# Sheet1.net
KiCad netlist of a schematic drawn in Altium Designer
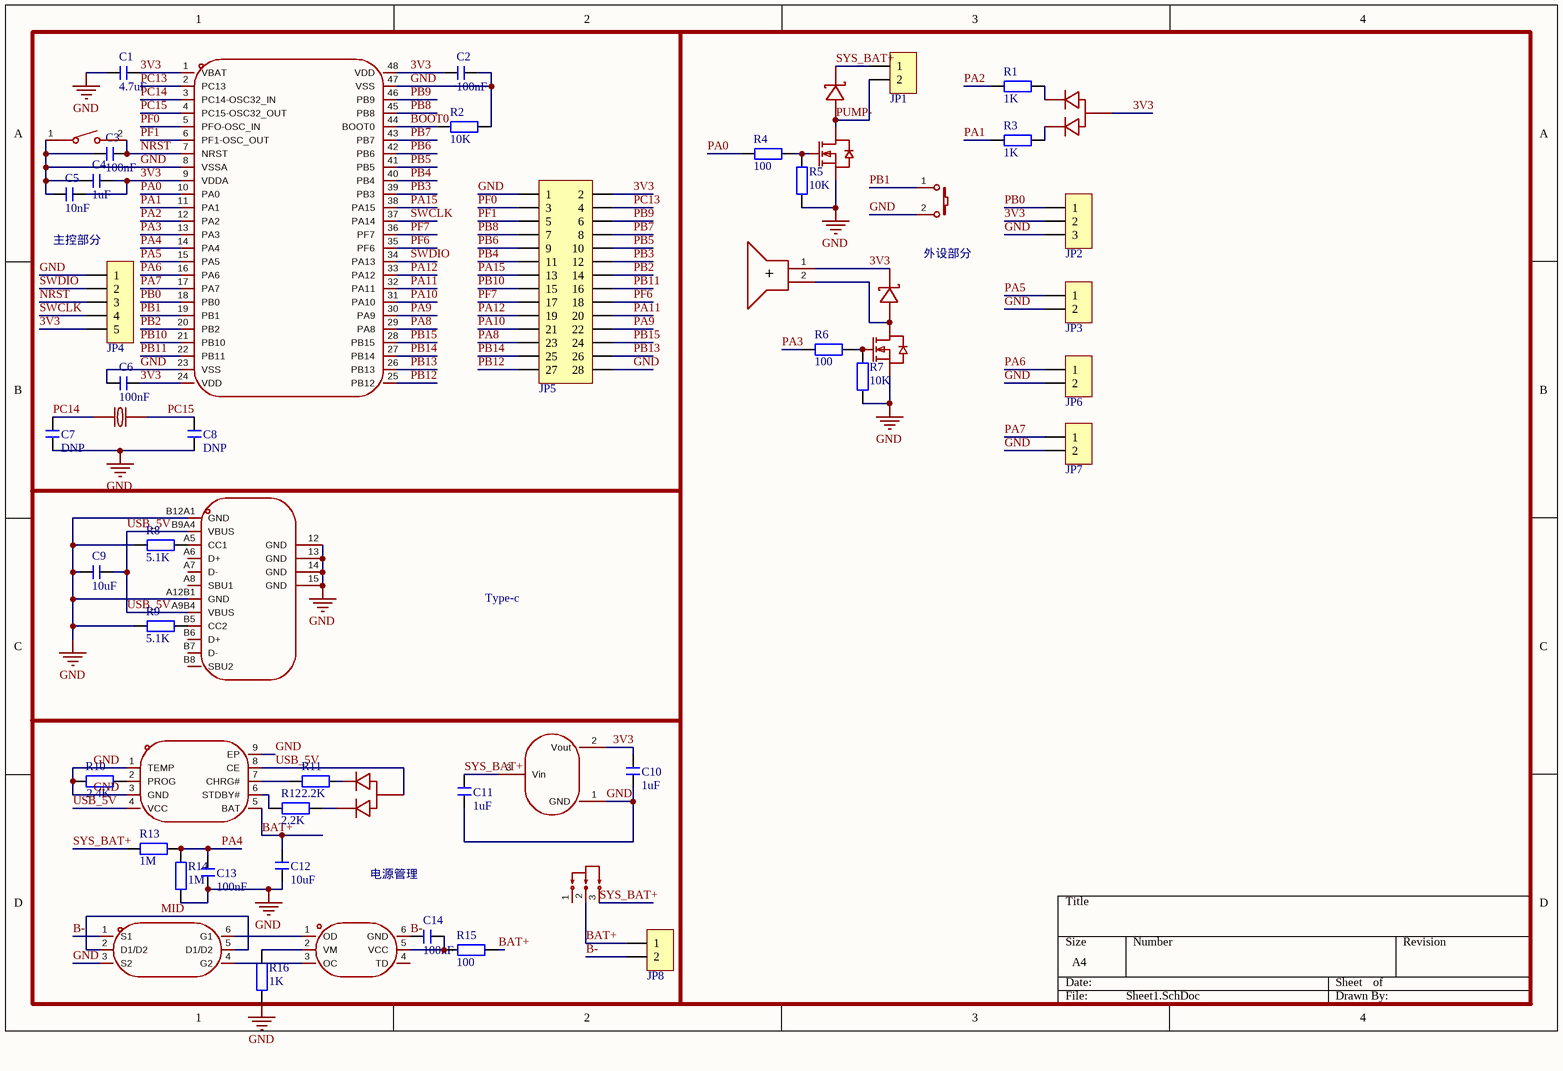
[diagram p0: Sheet1.SchDoc]

(export (version "E")
  (design (tool "Eeschema 10.0.6"))
  (components
    (comp (ref "BUZZER1")
      (value "hnb09a03")
      (footprint "BUZ-TH_BD9.0-P5.00-D0.6-FD")
      (description "驱动方式:有源(内含驱动线路);构造类型:电磁式;额定电压:3V;频率:3kHz;声压(SPL):85dB;")
      (fields (field (name "MANUFACTURER") "华能") (field (name "MANUFACTURERPART") "HNB09A03"))
      (libsource (lib "altium-import") (part "root_2_mirrored_hnb09a03_"))
    )
    (comp (ref "C1")
      (value "4.7uF")
      (footprint "C 0603_L")
      (description "贴片电容")
      (libsource (lib "0.1 - 电阻-电容-电感") (part "C"))
    )
    (comp (ref "C2")
      (value "100nF")
      (footprint "C 0603_L")
      (description "贴片电容")
      (libsource (lib "0.1 - 电阻-电容-电感") (part "C"))
    )
    (comp (ref "C3")
      (value "100nF")
      (footprint "C 0603_L")
      (description "贴片电容")
      (libsource (lib "0.1 - 电阻-电容-电感") (part "C"))
    )
    (comp (ref "C4")
      (value "1uF")
      (footprint "C 0603_L")
      (description "贴片电容")
      (libsource (lib "0.1 - 电阻-电容-电感") (part "C"))
    )
    (comp (ref "C5")
      (value "10nF")
      (footprint "C 0603_L")
      (description "贴片电容")
      (libsource (lib "0.1 - 电阻-电容-电感") (part "C"))
    )
    (comp (ref "C6")
      (value "100nF")
      (footprint "C 0603_L")
      (description "贴片电容")
      (libsource (lib "0.1 - 电阻-电容-电感") (part "C"))
    )
    (comp (ref "C7")
      (value "DNP")
      (footprint "C 0603_L")
      (description "贴片电容")
      (libsource (lib "0.1 - 电阻-电容-电感") (part "C"))
    )
    (comp (ref "C8")
      (value "DNP")
      (footprint "C 0603_L")
      (description "贴片电容")
      (libsource (lib "0.1 - 电阻-电容-电感") (part "C"))
    )
    (comp (ref "C9")
      (value "10uF")
      (footprint "C 0603_L")
      (description "贴片电容")
      (libsource (lib "Schlib1") (part "C"))
    )
    (comp (ref "C10")
      (value "1uF")
      (footprint "C 0603_L")
      (description "贴片电容")
      (libsource (lib "Schlib1") (part "C"))
    )
    (comp (ref "C11")
      (value "1uF")
      (footprint "C 0603_L")
      (description "贴片电容")
      (libsource (lib "Schlib1") (part "C"))
    )
    (comp (ref "C12")
      (value "10uF")
      (footprint "C 0603_L")
      (description "贴片电容")
      (libsource (lib "0.1 - 电阻-电容-电感") (part "C"))
    )
    (comp (ref "C13")
      (value "100nF")
      (footprint "C 0603_L")
      (description "贴片电容")
      (libsource (lib "0.1 - 电阻-电容-电感") (part "C"))
    )
    (comp (ref "C14")
      (value "100nF")
      (footprint "C 0603_L")
      (description "贴片电容")
      (libsource (lib "0.1 - 电阻-电容-电感") (part "C"))
    )
    (comp (ref "Charge_LED")
      (value "tj-l5fytxhtcylc2r2g-a5")
      (footprint "LED-TH_3P-BD5.9-P2.54-BI")
      (fields
        (field (name "MANUFACTURER") "TOGIALED(统佳)")
        (field (name "MANUFACTURERPART") "TJ-L5FYTXHTCYLC2R2G-A5")
      )
      (libsource (lib "altium-import") (part "root_3_tj-l5fytxhtcylc2r2g-a5_"))
    )
    (comp (ref "D1")
      (value "ss14_c83852")
      (footprint "SMA_L4.3-W2.6-LS5.2-RD")
      (description "正向压降(Vf):500mV@1A;直流反向耐压(Vr):40V;整流电流:1A;")
      (fields (field (name "MANUFACTURER") "onsemi(安森美)") (field (name "MANUFACTURERPART") "SS14"))
      (libsource (lib "Schlib1") (part "ss14_c83852"))
    )
    (comp (ref "D2")
      (value "ss14_c83852")
      (footprint "SMA_L4.3-W2.6-LS5.2-RD")
      (description "正向压降(Vf):500mV@1A;直流反向耐压(Vr):40V;整流电流:1A;")
      (fields (field (name "MANUFACTURER") "onsemi(安森美)") (field (name "MANUFACTURERPART") "SS14"))
      (libsource (lib "Schlib1") (part "ss14_c83852"))
    )
    (comp (ref "Function_LED")
      (value "tj-l5fytxhtcylc2r2g-a5")
      (footprint "LED-TH_3P-BD5.9-P2.54-BI")
      (fields
        (field (name "MANUFACTURER") "TOGIALED(统佳)")
        (field (name "MANUFACTURERPART") "TJ-L5FYTXHTCYLC2R2G-A5")
      )
      (libsource (lib "altium-import") (part "root_3_tj-l5fytxhtcylc2r2g-a5_"))
    )
    (comp (ref "JP1")
      (value "HDR-1X2")
      (footprint "XH2.54-LI-2P")
      (description "2P接插件")
      (fields (field (name "版权归属") "封装库来自淘宝 ID：黄晶宝石"))
      (libsource (lib "5.3 - 接插件-脚距2.54 (100mil) ") (part "Header 2"))
    )
    (comp (ref "JP2")
      (value "HDR-1X3")
      (footprint "HDR2.54-LI-3P")
      (description "3P接插件")
      (fields (field (name "版权归属") "封装库来自淘宝 ID：黄晶宝石"))
      (libsource (lib "5.3 - 接插件-脚距2.54 (100mil) ") (part "Header 3"))
    )
    (comp (ref "JP3")
      (value "HDR-1X2")
      (footprint "XH2.54-LI-2P")
      (description "2P接插件")
      (fields (field (name "版权归属") "封装库来自淘宝 ID：黄晶宝石"))
      (libsource (lib "5.3 - 接插件-脚距2.54 (100mil) ") (part "Header 2"))
    )
    (comp (ref "JP4")
      (value "HDR-1X5")
      (footprint "HDR2.54-LI-5P")
      (description "5P接插件")
      (fields (field (name "版权归属") "封装库来自淘宝 ID：黄晶宝石"))
      (libsource (lib "5.3 - 接插件-脚距2.54 (100mil) ") (part "Header 5"))
    )
    (comp (ref "JP5")
      (value "Header 2X11")
      (footprint "HDR2.54-LI-2x14P")
      (description "14*2P接插件")
      (fields (field (name "版权归属") "源创客"))
      (libsource (lib "5.3 - 接插件-脚距2.54 (100mil) ") (part "Header 14X2"))
    )
    (comp (ref "JP6")
      (value "HDR-1X2")
      (footprint "XH2.54-LI-2P")
      (description "2P接插件")
      (fields (field (name "版权归属") "封装库来自淘宝 ID：黄晶宝石"))
      (libsource (lib "5.3 - 接插件-脚距2.54 (100mil) ") (part "Header 2"))
    )
    (comp (ref "JP7")
      (value "HDR-1X2")
      (footprint "XH2.54-LI-2P")
      (description "2P接插件")
      (fields (field (name "版权归属") "封装库来自淘宝 ID：黄晶宝石"))
      (libsource (lib "5.3 - 接插件-脚距2.54 (100mil) ") (part "Header 2"))
    )
    (comp (ref "JP8")
      (value "HDR-1X2")
      (footprint "XH2.54-LI-2P")
      (description "2P接插件")
      (fields (field (name "版权归属") "封装库来自淘宝 ID：黄晶宝石"))
      (libsource (lib "5.3 - 接插件-脚距2.54 (100mil) ") (part "Header 2"))
    )
    (comp (ref "Q1")
      (value "ao3400a_c347475")
      (footprint "SOT-23-3_L2.9-W1.3-P1.90-LS2.4-BR")
      (description "数量:1个N沟道;漏源电压(Vdss):30V;连续漏极电流(Id):5.8A;导通电阻(RDS(on)):17mΩ@10V;耗散功率(Pd):1.4W;阈值电压(Vgs(th)):1.1V;")
      (fields (field (name "MANUFACTURER") "UMW(友台半导体)") (field (name "MANUFACTURERPART") "AO3400A"))
      (libsource (lib "Schlib1") (part "ao3400a_c347475"))
    )
    (comp (ref "Q2")
      (value "ao3400a_c347475")
      (footprint "SOT-23-3_L2.9-W1.3-P1.90-LS2.4-BR")
      (description "数量:1个N沟道;漏源电压(Vdss):30V;连续漏极电流(Id):5.8A;导通电阻(RDS(on)):17mΩ@10V;耗散功率(Pd):1.4W;阈值电压(Vgs(th)):1.1V;")
      (fields (field (name "MANUFACTURER") "UMW(友台半导体)") (field (name "MANUFACTURERPART") "AO3400A"))
      (libsource (lib "Schlib1") (part "ao3400a_c347475"))
    )
    (comp (ref "Q3")
      (value "fs8205a")
      (footprint "SOT-23-6_L2.9-W1.6-P0.95-LS2.8-BR")
      (fields (field (name "MANUFACTURER") "TECH PUBLIC(台舟)") (field (name "MANUFACTURERPART") "FS8205A"))
      (libsource (lib "Schlib1") (part "fs8205a"))
    )
    (comp (ref "R1")
      (value "1K")
      (footprint "R 0603_L")
      (description "贴片电阻")
      (fields (field (name "版权归属") "来自淘宝 ID：黄晶宝石"))
      (libsource (lib "0.1 - 电阻-电容-电感") (part "R"))
    )
    (comp (ref "R2")
      (value "10K")
      (footprint "R 0603_L")
      (description "贴片电阻")
      (fields (field (name "版权归属") "来自淘宝 ID：黄晶宝石"))
      (libsource (lib "0.1 - 电阻-电容-电感") (part "R"))
    )
    (comp (ref "R3")
      (value "1K")
      (footprint "R 0603_L")
      (description "贴片电阻")
      (fields (field (name "版权归属") "来自淘宝 ID：黄晶宝石"))
      (libsource (lib "0.1 - 电阻-电容-电感") (part "R"))
    )
    (comp (ref "R4")
      (value "100")
      (footprint "R 0603_L")
      (description "贴片电阻")
      (fields (field (name "版权归属") "来自淘宝 ID：黄晶宝石"))
      (libsource (lib "0.1 - 电阻-电容-电感") (part "R"))
    )
    (comp (ref "R5")
      (value "10K")
      (footprint "R 0603_L")
      (description "贴片电阻")
      (fields (field (name "版权归属") "来自淘宝 ID：黄晶宝石"))
      (libsource (lib "0.1 - 电阻-电容-电感") (part "R"))
    )
    (comp (ref "R6")
      (value "100")
      (footprint "R 0603_L")
      (description "贴片电阻")
      (fields (field (name "版权归属") "来自淘宝 ID：黄晶宝石"))
      (libsource (lib "0.1 - 电阻-电容-电感") (part "R"))
    )
    (comp (ref "R7")
      (value "10K")
      (footprint "R 0603_L")
      (description "贴片电阻")
      (fields (field (name "版权归属") "来自淘宝 ID：黄晶宝石"))
      (libsource (lib "0.1 - 电阻-电容-电感") (part "R"))
    )
    (comp (ref "R8")
      (value "5.1K")
      (footprint "R 0603_L")
      (description "贴片电阻")
      (fields (field (name "版权归属") "来自淘宝 ID：黄晶宝石"))
      (libsource (lib "0.1 - 电阻-电容-电感") (part "R"))
    )
    (comp (ref "R9")
      (value "5.1K")
      (footprint "R 0603_L")
      (description "贴片电阻")
      (fields (field (name "版权归属") "来自淘宝 ID：黄晶宝石"))
      (libsource (lib "0.1 - 电阻-电容-电感") (part "R"))
    )
    (comp (ref "R10")
      (value "2.4K")
      (footprint "R 0603_L")
      (description "贴片电阻")
      (fields (field (name "版权归属") "来自淘宝 ID：黄晶宝石"))
      (libsource (lib "0.1 - 电阻-电容-电感") (part "R"))
    )
    (comp (ref "R11")
      (value "2.2K")
      (footprint "R 0603_L")
      (description "贴片电阻")
      (fields (field (name "版权归属") "来自淘宝 ID：黄晶宝石"))
      (libsource (lib "0.1 - 电阻-电容-电感") (part "R"))
    )
    (comp (ref "R12")
      (value "2.2K")
      (footprint "R 0603_L")
      (description "贴片电阻")
      (fields (field (name "版权归属") "来自淘宝 ID：黄晶宝石"))
      (libsource (lib "0.1 - 电阻-电容-电感") (part "R"))
    )
    (comp (ref "R13")
      (value "1M")
      (footprint "R 0603_L")
      (description "贴片电阻")
      (fields (field (name "版权归属") "来自淘宝 ID：黄晶宝石"))
      (libsource (lib "0.1 - 电阻-电容-电感") (part "R"))
    )
    (comp (ref "R14")
      (value "1M")
      (footprint "R 0603_L")
      (description "贴片电阻")
      (fields (field (name "版权归属") "来自淘宝 ID：黄晶宝石"))
      (libsource (lib "0.1 - 电阻-电容-电感") (part "R"))
    )
    (comp (ref "R15")
      (value "100")
      (footprint "R 0603_L")
      (description "贴片电阻")
      (fields (field (name "版权归属") "来自淘宝 ID：黄晶宝石"))
      (libsource (lib "0.1 - 电阻-电容-电感") (part "R"))
    )
    (comp (ref "R16")
      (value "1K")
      (footprint "R 0603_L")
      (description "贴片电阻")
      (fields (field (name "版权归属") "来自淘宝 ID：黄晶宝石"))
      (libsource (lib "0.1 - 电阻-电容-电感") (part "R"))
    )
    (comp (ref "SW1")
      (value "ts-1088-ar02016")
      (footprint "SW-SMD_L3.9-W3.0-P4.45")
      (fields (field (name "MANUFACTURER") "XUNPU(讯普)") (field (name "MANUFACTURERPART") "TS-1088-AR02016"))
      (libsource (lib "Schlib1") (part "ts-1088-ar02016"))
    )
    (comp (ref "SW2")
      (value "mx1a-11nw")
      (footprint "SW-TH_MX1A-11NW")
      (fields (field (name "MANUFACTURER") "CHERRY") (field (name "MANUFACTURERPART") "MX1A-11NW"))
      (libsource (lib "altium-import") (part "root_3_mx1a-11nw_"))
    )
    (comp (ref "U1")
      (value "stm32f031c6t6")
      (footprint "LQFP-48_L7.0-W7.0-P0.50-LS9.0-BL")
      (description "CPU内核:ARM Cortex-M0;CPU最大主频:48MHz;CPU位数:32 Bit;")
      (fields (field (name "MANUFACTURER") "ST(意法半导体)") (field (name "MANUFACTURERPART") "STM32F031C6T6"))
      (libsource (lib "Schlib1") (part "stm32f031c6t6"))
    )
    (comp (ref "U2")
      (value "xc6206p332mr-g_c5446")
      (footprint "SOT-23-3_L2.9-W1.6-P1.90-LS2.8-BR")
      (description "输出极性:正极;工作电压:6V;输出电压:3.3V;输出电流:200mA;电源纹波抑制比(PSRR):-;输出类型:固定;")
      (fields (field (name "MANUFACTURER") "TOREX(特瑞仕)") (field (name "MANUFACTURERPART") "XC6206P332MR-G"))
      (libsource (lib "Schlib1") (part "xc6206p332mr-g_c5446"))
    )
    (comp (ref "U3")
      (value "tp4056_c382139")
      (footprint "ESOP-8_L4.9-W3.9-P1.27-LS6.0-BL-EP")
      (description "工作电压:4V~6V;最大充电电流:1A;电池类型:锂电池;电池节数:1;")
      (fields (field (name "MANUFACTURER") "TPOWER(天源)") (field (name "MANUFACTURERPART") "TP4056"))
      (libsource (lib "Schlib1") (part "tp4056_c382139"))
    )
    (comp (ref "U4")
      (value "hx ss12d10g5")
      (footprint "SW-TH_3P-P4.80-HX-SS12D10G4")
      (description "电路结构:单刀双掷;安装方式:直插;开关颜色:黑色;额定电流:2A;额定电压:125V;工作寿命:1万次;")
      (fields (field (name "MANUFACTURER") "hanxia(韩下)") (field (name "MANUFACTURERPART") "HX SS12D10G5"))
      (libsource (lib "altium-import") (part "root_0_hx ss12d10g5_"))
    )
    (comp (ref "U5")
      (value "dw01a_c351410")
      (footprint "SOT-23-6_L2.9-W1.6-P0.95-LS2.8-BL")
      (description "工作电压:300mV~10V;最大充电电流:-;电池类型:锂电池;电池节数:1;")
      (fields (field (name "MANUFACTURER") "PUOLOP(迪浦)") (field (name "MANUFACTURERPART") "DW01A"))
      (libsource (lib "Schlib1") (part "dw01a_c351410"))
    )
    (comp (ref "USB1")
      (value "typec-16p_c53207138")
      (footprint "USB-C-SMD_TYPEC-16P_C53207138")
      (description "连接器类型:Type-C;协议标准:-;公母:母;安装方式:卧贴;触点数量:16P;端口数量:1;额定电流 - 电源:3A;工作温度:-40℃~+85℃;")
      (fields (field (name "MANUFACTURER") "BXCONN(宝讯)") (field (name "MANUFACTURERPART") "TYPEC-16P"))
      (libsource (lib "Schlib1") (part "typec-16p_c53207138"))
    )
    (comp (ref "X1")
      (value "q13fc13500004_c32346")
      (footprint "FC-135R_L3.2-W1.5")
      (description "晶振类型:贴片晶振;频率:32.768kHz;常温频差:±20ppm;负载电容:12.5pF;")
      (fields (field (name "MANUFACTURER") "EPSON(爱普生)") (field (name "MANUFACTURERPART") "Q13FC13500004"))
      (libsource (lib "altium-import") (part "root_0_q13fc13500004_c32346_"))
    )
  )
  (nets
    (net (code "1") (name "/3V3") (class "Default")
      (node (ref "BUZZER1") (pin "1") (pinfunction "+_1") (pintype "passive"))
      (node (ref "C1") (pin "2") (pinfunction "2_2") (pintype "passive"))
      (node (ref "C10") (pin "2") (pinfunction "2_2") (pintype "passive"))
      (node (ref "C2") (pin "1") (pinfunction "1_1") (pintype "passive"))
      (node (ref "C4") (pin "2") (pinfunction "2_2") (pintype "passive"))
      (node (ref "C5") (pin "2") (pinfunction "2_2") (pintype "passive"))
      (node (ref "C6") (pin "2") (pinfunction "2_2") (pintype "passive"))
      (node (ref "D2") (pin "1") (pinfunction "K_1") (pintype "passive"))
      (node (ref "Function_LED") (pin "2") (pinfunction "+_2") (pintype "passive"))
      (node (ref "JP2") (pin "2") (pinfunction "2_2") (pintype "passive"))
      (node (ref "JP4") (pin "5") (pinfunction "5_5") (pintype "passive"))
      (node (ref "JP5") (pin "2") (pinfunction "2_2") (pintype "passive"))
      (node (ref "U1") (pin "1") (pinfunction "VBAT_1") (pintype "passive"))
      (node (ref "U1") (pin "24") (pinfunction "VDD_24") (pintype "passive"))
      (node (ref "U1") (pin "48") (pinfunction "VDD_48") (pintype "passive"))
      (node (ref "U1") (pin "9") (pinfunction "VDDA_9") (pintype "passive"))
      (node (ref "U2") (pin "2") (pinfunction "Vout_2") (pintype "passive"))
    )
    (net (code "2") (name "/B-") (class "Default")
      (node (ref "C14") (pin "2") (pinfunction "2_2") (pintype "passive"))
      (node (ref "JP8") (pin "2") (pinfunction "2_2") (pintype "passive"))
      (node (ref "Q3") (pin "1") (pinfunction "S1_1") (pintype "passive"))
      (node (ref "U5") (pin "6") (pinfunction "GND_6") (pintype "passive"))
    )
    (net (code "3") (name "/BAT+") (class "Default")
      (node (ref "C12") (pin "2") (pinfunction "2_2") (pintype "passive"))
      (node (ref "JP8") (pin "1") (pinfunction "1_1") (pintype "passive"))
      (node (ref "R15") (pin "1") (pinfunction "1_1") (pintype "passive"))
      (node (ref "U3") (pin "5") (pinfunction "BAT_5") (pintype "passive"))
      (node (ref "U4") (pin "2") (pinfunction "2_2") (pintype "passive"))
    )
    (net (code "4") (name "/BOOT0") (class "Default")
      (node (ref "R2") (pin "1") (pinfunction "1_1") (pintype "passive"))
      (node (ref "U1") (pin "44") (pinfunction "BOOT0_44") (pintype "passive"))
    )
    (net (code "5") (name "/MID") (class "Default")
      (node (ref "Q3") (pin "2") (pinfunction "D1/D2_2") (pintype "passive"))
      (node (ref "Q3") (pin "5") (pinfunction "D1/D2_5") (pintype "passive"))
    )
    (net (code "6") (name "/NRST") (class "Default")
      (node (ref "C3") (pin "2") (pinfunction "2_2") (pintype "passive"))
      (node (ref "JP4") (pin "3") (pinfunction "3_3") (pintype "passive"))
      (node (ref "SW1") (pin "2") (pinfunction "2_2") (pintype "passive"))
      (node (ref "U1") (pin "7") (pinfunction "NRST_7") (pintype "passive"))
    )
    (net (code "7") (name "/PA0") (class "Default")
      (node (ref "R4") (pin "1") (pinfunction "1_1") (pintype "passive"))
      (node (ref "U1") (pin "10") (pinfunction "PA0_10") (pintype "passive"))
    )
    (net (code "8") (name "/PA1") (class "Default")
      (node (ref "R3") (pin "2") (pinfunction "2_2") (pintype "passive"))
      (node (ref "U1") (pin "11") (pinfunction "PA1_11") (pintype "passive"))
    )
    (net (code "9") (name "/PA2") (class "Default")
      (node (ref "R1") (pin "2") (pinfunction "2_2") (pintype "passive"))
      (node (ref "U1") (pin "12") (pinfunction "PA2_12") (pintype "passive"))
    )
    (net (code "10") (name "/PA3") (class "Default")
      (node (ref "R6") (pin "2") (pinfunction "2_2") (pintype "passive"))
      (node (ref "U1") (pin "13") (pinfunction "PA3_13") (pintype "passive"))
    )
    (net (code "11") (name "/PA4") (class "Default")
      (node (ref "C13") (pin "2") (pinfunction "2_2") (pintype "passive"))
      (node (ref "R13") (pin "1") (pinfunction "1_1") (pintype "passive"))
      (node (ref "R14") (pin "2") (pinfunction "2_2") (pintype "passive"))
      (node (ref "U1") (pin "14") (pinfunction "PA4_14") (pintype "passive"))
    )
    (net (code "12") (name "/PA5") (class "Default")
      (node (ref "JP3") (pin "1") (pinfunction "1_1") (pintype "passive"))
      (node (ref "U1") (pin "15") (pinfunction "PA5_15") (pintype "passive"))
    )
    (net (code "13") (name "/PA6") (class "Default")
      (node (ref "JP6") (pin "1") (pinfunction "1_1") (pintype "passive"))
      (node (ref "U1") (pin "16") (pinfunction "PA6_16") (pintype "passive"))
    )
    (net (code "14") (name "/PA7") (class "Default")
      (node (ref "JP7") (pin "1") (pinfunction "1_1") (pintype "passive"))
      (node (ref "U1") (pin "17") (pinfunction "PA7_17") (pintype "passive"))
    )
    (net (code "15") (name "/PA8") (class "Default")
      (node (ref "JP5") (pin "23") (pinfunction "23_23") (pintype "passive"))
      (node (ref "U1") (pin "29") (pinfunction "PA8_29") (pintype "passive"))
    )
    (net (code "16") (name "/PA9") (class "Default")
      (node (ref "JP5") (pin "22") (pinfunction "22_22") (pintype "passive"))
      (node (ref "U1") (pin "30") (pinfunction "PA9_30") (pintype "passive"))
    )
    (net (code "17") (name "/PA10") (class "Default")
      (node (ref "JP5") (pin "21") (pinfunction "21_21") (pintype "passive"))
      (node (ref "U1") (pin "31") (pinfunction "PA10_31") (pintype "passive"))
    )
    (net (code "18") (name "/PA11") (class "Default")
      (node (ref "JP5") (pin "20") (pinfunction "20_20") (pintype "passive"))
      (node (ref "U1") (pin "32") (pinfunction "PA11_32") (pintype "passive"))
    )
    (net (code "19") (name "/PA12") (class "Default")
      (node (ref "JP5") (pin "19") (pinfunction "19_19") (pintype "passive"))
      (node (ref "U1") (pin "33") (pinfunction "PA12_33") (pintype "passive"))
    )
    (net (code "20") (name "/PA15") (class "Default")
      (node (ref "JP5") (pin "13") (pinfunction "13_13") (pintype "passive"))
      (node (ref "U1") (pin "38") (pinfunction "PA15_38") (pintype "passive"))
    )
    (net (code "21") (name "/PB0") (class "Default")
      (node (ref "JP2") (pin "1") (pinfunction "1_1") (pintype "passive"))
      (node (ref "U1") (pin "18") (pinfunction "PB0_18") (pintype "passive"))
    )
    (net (code "22") (name "/PB1") (class "Default")
      (node (ref "SW2") (pin "1") (pinfunction "1_1") (pintype "passive"))
      (node (ref "U1") (pin "19") (pinfunction "PB1_19") (pintype "passive"))
    )
    (net (code "23") (name "/PB2") (class "Default")
      (node (ref "JP5") (pin "14") (pinfunction "14_14") (pintype "passive"))
      (node (ref "U1") (pin "20") (pinfunction "PB2_20") (pintype "passive"))
    )
    (net (code "24") (name "/PB3") (class "Default")
      (node (ref "JP5") (pin "12") (pinfunction "12_12") (pintype "passive"))
      (node (ref "U1") (pin "39") (pinfunction "PB3_39") (pintype "passive"))
    )
    (net (code "25") (name "/PB4") (class "Default")
      (node (ref "JP5") (pin "11") (pinfunction "11_11") (pintype "passive"))
      (node (ref "U1") (pin "40") (pinfunction "PB4_40") (pintype "passive"))
    )
    (net (code "26") (name "/PB5") (class "Default")
      (node (ref "JP5") (pin "10") (pinfunction "10_10") (pintype "passive"))
      (node (ref "U1") (pin "41") (pinfunction "PB5_41") (pintype "passive"))
    )
    (net (code "27") (name "/PB6") (class "Default")
      (node (ref "JP5") (pin "9") (pinfunction "9_9") (pintype "passive"))
      (node (ref "U1") (pin "42") (pinfunction "PB6_42") (pintype "passive"))
    )
    (net (code "28") (name "/PB7") (class "Default")
      (node (ref "JP5") (pin "8") (pinfunction "8_8") (pintype "passive"))
      (node (ref "U1") (pin "43") (pinfunction "PB7_43") (pintype "passive"))
    )
    (net (code "29") (name "/PB8") (class "Default")
      (node (ref "JP5") (pin "7") (pinfunction "7_7") (pintype "passive"))
      (node (ref "U1") (pin "45") (pinfunction "PB8_45") (pintype "passive"))
    )
    (net (code "30") (name "/PB9") (class "Default")
      (node (ref "JP5") (pin "6") (pinfunction "6_6") (pintype "passive"))
      (node (ref "U1") (pin "46") (pinfunction "PB9_46") (pintype "passive"))
    )
    (net (code "31") (name "/PB10") (class "Default")
      (node (ref "JP5") (pin "15") (pinfunction "15_15") (pintype "passive"))
      (node (ref "U1") (pin "21") (pinfunction "PB10_21") (pintype "passive"))
    )
    (net (code "32") (name "/PB11") (class "Default")
      (node (ref "JP5") (pin "16") (pinfunction "16_16") (pintype "passive"))
      (node (ref "U1") (pin "22") (pinfunction "PB11_22") (pintype "passive"))
    )
    (net (code "33") (name "/PB12") (class "Default")
      (node (ref "JP5") (pin "27") (pinfunction "27_27") (pintype "passive"))
      (node (ref "U1") (pin "25") (pinfunction "PB12_25") (pintype "passive"))
    )
    (net (code "34") (name "/PB13") (class "Default")
      (node (ref "JP5") (pin "26") (pinfunction "26_26") (pintype "passive"))
      (node (ref "U1") (pin "26") (pinfunction "PB13_26") (pintype "passive"))
    )
    (net (code "35") (name "/PB14") (class "Default")
      (node (ref "JP5") (pin "25") (pinfunction "25_25") (pintype "passive"))
      (node (ref "U1") (pin "27") (pinfunction "PB14_27") (pintype "passive"))
    )
    (net (code "36") (name "/PB15") (class "Default")
      (node (ref "JP5") (pin "24") (pinfunction "24_24") (pintype "passive"))
      (node (ref "U1") (pin "28") (pinfunction "PB15_28") (pintype "passive"))
    )
    (net (code "37") (name "/PC13") (class "Default")
      (node (ref "JP5") (pin "4") (pinfunction "4_4") (pintype "passive"))
      (node (ref "U1") (pin "2") (pinfunction "PC13_2") (pintype "passive"))
    )
    (net (code "38") (name "/PC14") (class "Default")
      (node (ref "C7") (pin "2") (pinfunction "2_2") (pintype "passive"))
      (node (ref "U1") (pin "3") (pinfunction "PC14-OSC32_IN_3") (pintype "passive"))
      (node (ref "X1") (pin "1") (pinfunction "1_1") (pintype "passive"))
    )
    (net (code "39") (name "/PC15") (class "Default")
      (node (ref "C8") (pin "2") (pinfunction "2_2") (pintype "passive"))
      (node (ref "U1") (pin "4") (pinfunction "PC15-OSC32_OUT_4") (pintype "passive"))
      (node (ref "X1") (pin "2") (pinfunction "2_2") (pintype "passive"))
    )
    (net (code "40") (name "/PF0") (class "Default")
      (node (ref "JP5") (pin "3") (pinfunction "3_3") (pintype "passive"))
      (node (ref "U1") (pin "5") (pinfunction "PFO-OSC_IN_5") (pintype "passive"))
    )
    (net (code "41") (name "/PF1") (class "Default")
      (node (ref "JP5") (pin "5") (pinfunction "5_5") (pintype "passive"))
      (node (ref "U1") (pin "6") (pinfunction "PF1-OSC_OUT_6") (pintype "passive"))
    )
    (net (code "42") (name "/PF6") (class "Default")
      (node (ref "JP5") (pin "18") (pinfunction "18_18") (pintype "passive"))
      (node (ref "U1") (pin "35") (pinfunction "PF6_35") (pintype "passive"))
    )
    (net (code "43") (name "/PF7") (class "Default")
      (node (ref "JP5") (pin "17") (pinfunction "17_17") (pintype "passive"))
      (node (ref "U1") (pin "36") (pinfunction "PF7_36") (pintype "passive"))
    )
    (net (code "44") (name "/PUMP-") (class "Default")
      (node (ref "D1") (pin "2") (pinfunction "A_2") (pintype "passive"))
      (node (ref "JP1") (pin "2") (pinfunction "2_2") (pintype "passive"))
      (node (ref "Q1") (pin "3") (pinfunction "D_3") (pintype "passive"))
    )
    (net (code "45") (name "/SWCLK") (class "Default")
      (node (ref "JP4") (pin "4") (pinfunction "4_4") (pintype "passive"))
      (node (ref "U1") (pin "37") (pinfunction "PA14_37") (pintype "passive"))
    )
    (net (code "46") (name "/SWDIO") (class "Default")
      (node (ref "JP4") (pin "2") (pinfunction "2_2") (pintype "passive"))
      (node (ref "U1") (pin "34") (pinfunction "PA13_34") (pintype "passive"))
    )
    (net (code "47") (name "/SYS_BAT+") (class "Default")
      (node (ref "C11") (pin "2") (pinfunction "2_2") (pintype "passive"))
      (node (ref "D1") (pin "1") (pinfunction "K_1") (pintype "passive"))
      (node (ref "JP1") (pin "1") (pinfunction "1_1") (pintype "passive"))
      (node (ref "R13") (pin "2") (pinfunction "2_2") (pintype "passive"))
      (node (ref "U2") (pin "3") (pinfunction "Vin_3") (pintype "passive"))
      (node (ref "U4") (pin "3") (pinfunction "3_3") (pintype "passive"))
    )
    (net (code "48") (name "/USB_5V") (class "Default")
      (node (ref "C9") (pin "2") (pinfunction "2_2") (pintype "passive"))
      (node (ref "Charge_LED") (pin "2") (pinfunction "+_2") (pintype "passive"))
      (node (ref "U3") (pin "4") (pinfunction "VCC_4") (pintype "passive"))
      (node (ref "U3") (pin "8") (pinfunction "CE_8") (pintype "passive"))
      (node (ref "USB1") (pin "A9B4") (pinfunction "VBUS_A9B4") (pintype "passive"))
      (node (ref "USB1") (pin "B9A4") (pinfunction "VBUS_B9A4") (pintype "passive"))
    )
    (net (code "49") (name "GND") (class "Default")
      (node (ref "C1") (pin "1") (pinfunction "1_1") (pintype "passive"))
      (node (ref "C10") (pin "1") (pinfunction "1_1") (pintype "passive"))
      (node (ref "C11") (pin "1") (pinfunction "1_1") (pintype "passive"))
      (node (ref "C12") (pin "1") (pinfunction "1_1") (pintype "passive"))
      (node (ref "C13") (pin "1") (pinfunction "1_1") (pintype "passive"))
      (node (ref "C2") (pin "2") (pinfunction "2_2") (pintype "passive"))
      (node (ref "C3") (pin "1") (pinfunction "1_1") (pintype "passive"))
      (node (ref "C4") (pin "1") (pinfunction "1_1") (pintype "passive"))
      (node (ref "C5") (pin "1") (pinfunction "1_1") (pintype "passive"))
      (node (ref "C6") (pin "1") (pinfunction "1_1") (pintype "passive"))
      (node (ref "C7") (pin "1") (pinfunction "1_1") (pintype "passive"))
      (node (ref "C8") (pin "1") (pinfunction "1_1") (pintype "passive"))
      (node (ref "C9") (pin "1") (pinfunction "1_1") (pintype "passive"))
      (node (ref "JP2") (pin "3") (pinfunction "3_3") (pintype "passive"))
      (node (ref "JP3") (pin "2") (pinfunction "2_2") (pintype "passive"))
      (node (ref "JP4") (pin "1") (pinfunction "1_1") (pintype "passive"))
      (node (ref "JP5") (pin "1") (pinfunction "1_1") (pintype "passive"))
      (node (ref "JP5") (pin "28") (pinfunction "28_28") (pintype "passive"))
      (node (ref "JP6") (pin "2") (pinfunction "2_2") (pintype "passive"))
      (node (ref "JP7") (pin "2") (pinfunction "2_2") (pintype "passive"))
      (node (ref "Q1") (pin "2") (pinfunction "S_2") (pintype "passive"))
      (node (ref "Q2") (pin "2") (pinfunction "S_2") (pintype "passive"))
      (node (ref "Q3") (pin "3") (pinfunction "S2_3") (pintype "passive"))
      (node (ref "R10") (pin "1") (pinfunction "1_1") (pintype "passive"))
      (node (ref "R14") (pin "1") (pinfunction "1_1") (pintype "passive"))
      (node (ref "R16") (pin "1") (pinfunction "1_1") (pintype "passive"))
      (node (ref "R2") (pin "2") (pinfunction "2_2") (pintype "passive"))
      (node (ref "R5") (pin "1") (pinfunction "1_1") (pintype "passive"))
      (node (ref "R7") (pin "1") (pinfunction "1_1") (pintype "passive"))
      (node (ref "R8") (pin "1") (pinfunction "1_1") (pintype "passive"))
      (node (ref "R9") (pin "1") (pinfunction "1_1") (pintype "passive"))
      (node (ref "SW1") (pin "1") (pinfunction "1_1") (pintype "passive"))
      (node (ref "SW2") (pin "2") (pinfunction "2_2") (pintype "passive"))
      (node (ref "U1") (pin "23") (pinfunction "VSS_23") (pintype "passive"))
      (node (ref "U1") (pin "47") (pinfunction "VSS_47") (pintype "passive"))
      (node (ref "U1") (pin "8") (pinfunction "VSSA_8") (pintype "passive"))
      (node (ref "U2") (pin "1") (pinfunction "GND_1") (pintype "passive"))
      (node (ref "U3") (pin "1") (pinfunction "TEMP_1") (pintype "passive"))
      (node (ref "U3") (pin "3") (pinfunction "GND_3") (pintype "passive"))
      (node (ref "U3") (pin "9") (pinfunction "EP_9") (pintype "passive"))
      (node (ref "USB1") (pin "12") (pinfunction "GND_12") (pintype "passive"))
      (node (ref "USB1") (pin "13") (pinfunction "GND_13") (pintype "passive"))
      (node (ref "USB1") (pin "14") (pinfunction "GND_14") (pintype "passive"))
      (node (ref "USB1") (pin "15") (pinfunction "GND_15") (pintype "passive"))
      (node (ref "USB1") (pin "A12B1") (pinfunction "GND_A12B1") (pintype "passive"))
      (node (ref "USB1") (pin "B12A1") (pinfunction "GND_B12A1") (pintype "passive"))
    )
    (net (code "50") (name "Net-(BUZZER1--)") (class "Default")
      (node (ref "BUZZER1") (pin "2") (pinfunction "-_2") (pintype "passive"))
      (node (ref "D2") (pin "2") (pinfunction "A_2") (pintype "passive"))
      (node (ref "Q2") (pin "3") (pinfunction "D_3") (pintype "passive"))
    )
    (net (code "51") (name "Net-(Charge_LED--)") (class "Default")
      (node (ref "Charge_LED") (pin "1") (pinfunction "-_1") (pintype "passive"))
      (node (ref "R11") (pin "1") (pinfunction "1_1") (pintype "passive"))
    )
    (net (code "52") (name "Net-(Charge_LED-R)") (class "Default")
      (node (ref "Charge_LED") (pin "3") (pinfunction "R_3") (pintype "passive"))
      (node (ref "R12") (pin "1") (pinfunction "1_1") (pintype "passive"))
    )
    (net (code "53") (name "Net-(Function_LED--)") (class "Default")
      (node (ref "Function_LED") (pin "1") (pinfunction "-_1") (pintype "passive"))
      (node (ref "R1") (pin "1") (pinfunction "1_1") (pintype "passive"))
    )
    (net (code "54") (name "Net-(Function_LED-R)") (class "Default")
      (node (ref "Function_LED") (pin "3") (pinfunction "R_3") (pintype "passive"))
      (node (ref "R3") (pin "1") (pinfunction "1_1") (pintype "passive"))
    )
    (net (code "55") (name "Net-(Q1-G)") (class "Default")
      (node (ref "Q1") (pin "1") (pinfunction "G_1") (pintype "passive"))
      (node (ref "R4") (pin "2") (pinfunction "2_2") (pintype "passive"))
      (node (ref "R5") (pin "2") (pinfunction "2_2") (pintype "passive"))
    )
    (net (code "56") (name "Net-(Q2-G)") (class "Default")
      (node (ref "Q2") (pin "1") (pinfunction "G_1") (pintype "passive"))
      (node (ref "R6") (pin "1") (pinfunction "1_1") (pintype "passive"))
      (node (ref "R7") (pin "2") (pinfunction "2_2") (pintype "passive"))
    )
    (net (code "57") (name "Net-(Q3-G1)") (class "Default")
      (node (ref "Q3") (pin "6") (pinfunction "G1_6") (pintype "passive"))
      (node (ref "U5") (pin "1") (pinfunction "OD_1") (pintype "passive"))
    )
    (net (code "58") (name "Net-(Q3-G2)") (class "Default")
      (node (ref "Q3") (pin "4") (pinfunction "G2_4") (pintype "passive"))
      (node (ref "U5") (pin "3") (pinfunction "OC_3") (pintype "passive"))
    )
    (net (code "59") (name "Net-(U3-CHRG#)") (class "Default")
      (node (ref "R11") (pin "2") (pinfunction "2_2") (pintype "passive"))
      (node (ref "U3") (pin "7") (pinfunction "CHRG#_7") (pintype "passive"))
    )
    (net (code "60") (name "Net-(U3-PROG)") (class "Default")
      (node (ref "R10") (pin "2") (pinfunction "2_2") (pintype "passive"))
      (node (ref "U3") (pin "2") (pinfunction "PROG_2") (pintype "passive"))
    )
    (net (code "61") (name "Net-(U3-STDBY#)") (class "Default")
      (node (ref "R12") (pin "2") (pinfunction "2_2") (pintype "passive"))
      (node (ref "U3") (pin "6") (pinfunction "STDBY#_6") (pintype "passive"))
    )
    (net (code "62") (name "Net-(U5-VCC)") (class "Default")
      (node (ref "C14") (pin "1") (pinfunction "1_1") (pintype "passive"))
      (node (ref "R15") (pin "2") (pinfunction "2_2") (pintype "passive"))
      (node (ref "U5") (pin "5") (pinfunction "VCC_5") (pintype "passive"))
    )
    (net (code "63") (name "Net-(U5-VM)") (class "Default")
      (node (ref "R16") (pin "2") (pinfunction "2_2") (pintype "passive"))
      (node (ref "U5") (pin "2") (pinfunction "VM_2") (pintype "passive"))
    )
    (net (code "64") (name "Net-(USB1-CC1)") (class "Default")
      (node (ref "R8") (pin "2") (pinfunction "2_2") (pintype "passive"))
      (node (ref "USB1") (pin "A5") (pinfunction "CC1_A5") (pintype "passive"))
    )
    (net (code "65") (name "Net-(USB1-CC2)") (class "Default")
      (node (ref "R9") (pin "2") (pinfunction "2_2") (pintype "passive"))
      (node (ref "USB1") (pin "B5") (pinfunction "CC2_B5") (pintype "passive"))
    )
    (net (code "66") (name "unconnected-(U4-Pad1)") (class "Default")
      (node (ref "U4") (pin "1") (pinfunction "1_1") (pintype "passive"))
    )
    (net (code "67") (name "unconnected-(U5-TD-Pad4)") (class "Default")
      (node (ref "U5") (pin "4") (pinfunction "TD_4") (pintype "passive"))
    )
    (net (code "68") (name "unconnected-(USB1-D+-PadA6)") (class "Default")
      (node (ref "USB1") (pin "A6") (pinfunction "D+_A6") (pintype "passive"))
    )
    (net (code "69") (name "unconnected-(USB1-D+-PadB6)") (class "Default")
      (node (ref "USB1") (pin "B6") (pinfunction "D+_B6") (pintype "passive"))
    )
    (net (code "70") (name "unconnected-(USB1-D--PadA7)") (class "Default")
      (node (ref "USB1") (pin "A7") (pinfunction "D-_A7") (pintype "passive"))
    )
    (net (code "71") (name "unconnected-(USB1-D--PadB7)") (class "Default")
      (node (ref "USB1") (pin "B7") (pinfunction "D-_B7") (pintype "passive"))
    )
    (net (code "72") (name "unconnected-(USB1-SBU1-PadA8)") (class "Default")
      (node (ref "USB1") (pin "A8") (pinfunction "SBU1_A8") (pintype "passive"))
    )
    (net (code "73") (name "unconnected-(USB1-SBU2-PadB8)") (class "Default")
      (node (ref "USB1") (pin "B8") (pinfunction "SBU2_B8") (pintype "passive"))
    )
  )
)
